# voeding.net
KiCad netlist of a schematic drawn in Altium Designer
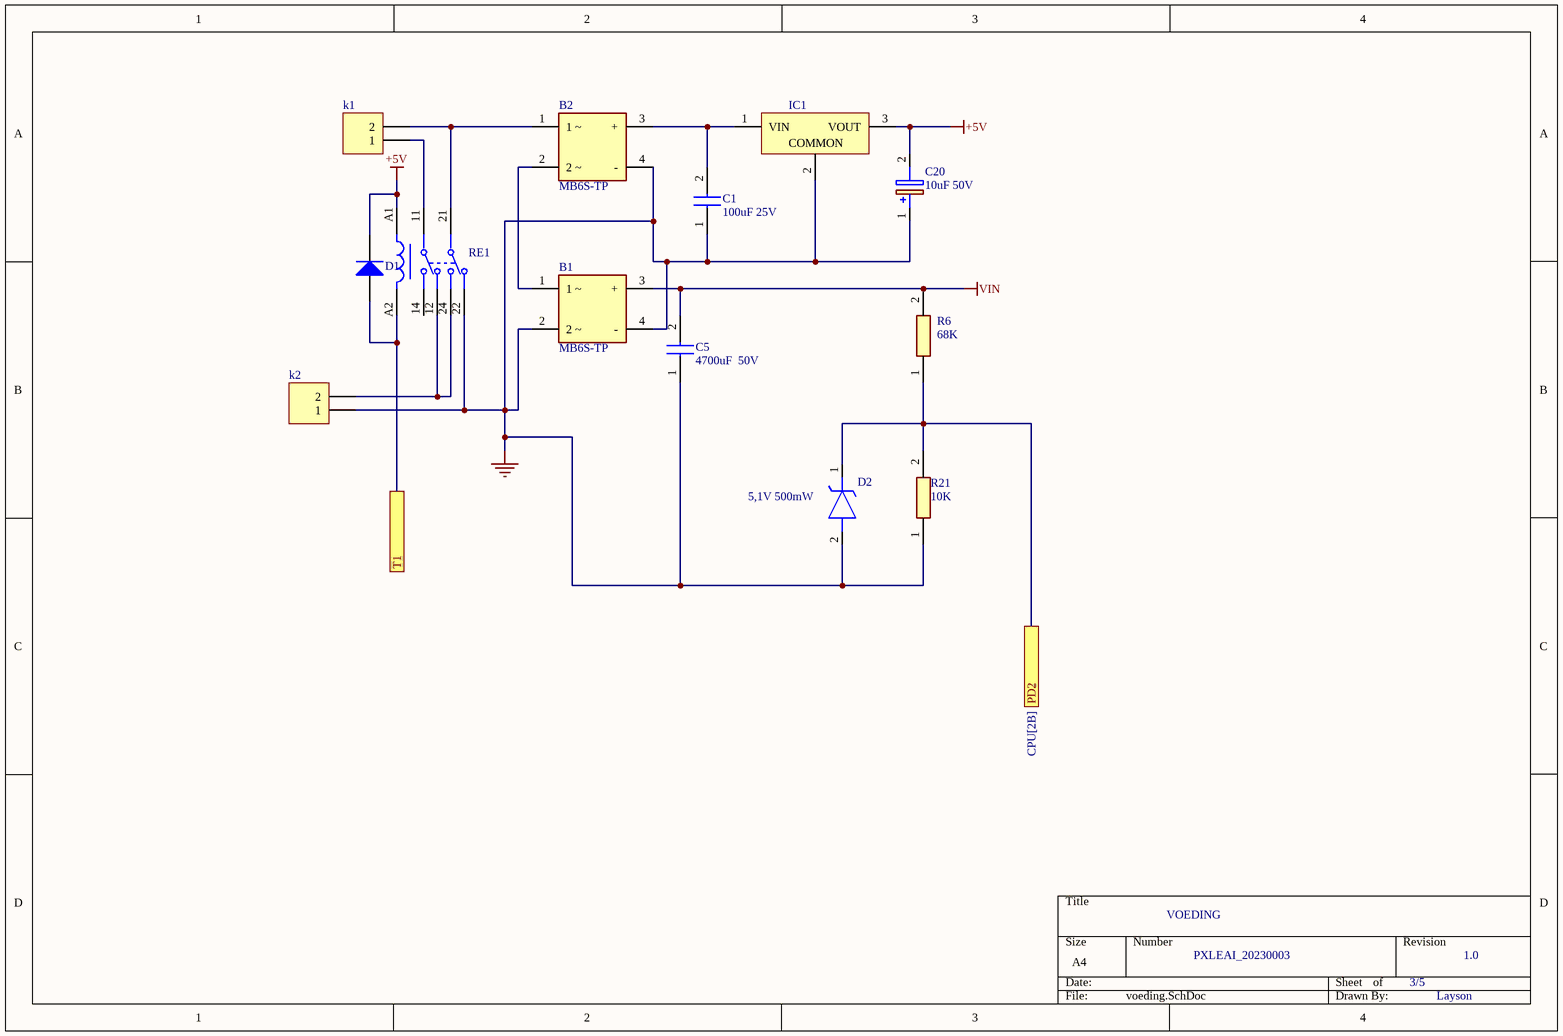
[diagram p0: voeding.SchDoc]

(export (version "E")
  (design (tool "Eeschema 10.0.6"))
  (components
    (comp (ref "B1")
      (value "MB6S-TP")
      (footprint "FP-MBS-1-MFG")
      (description "BRIDGE RECT 1P 600V 500MA MBS-1")
      (fields
        (field (name "OCTOPART") "https://octopart.com/mb6s-tp-mcc-733391")
        (field (name "MANUFACTURER") "MCC")
      )
      (libsource (lib "Altium Content Vault") (part "4d71835a231c4bf99e86ed7a78abdc8"))
    )
    (comp (ref "B2")
      (value "MB6S-TP")
      (footprint "FP-MBS-1-MFG")
      (description "BRIDGE RECT 1P 600V 500MA MBS-1")
      (fields
        (field (name "OCTOPART") "https://octopart.com/mb6s-tp-mcc-733391")
        (field (name "MANUFACTURER") "MCC")
      )
      (libsource (lib "Altium Content Vault") (part "4d71835a231c4bf99e86ed7a78abdc8"))
    )
    (comp (ref "C1")
      (value "100uF 25V")
      (footprint "SamacSys:MCGPR25V107M6.3X11")
      (description "Capacitor\r\nMCGPR25V107M6.3X11")
      (fields (field (name "MANUFACTURER_PART_NUMBER") "MCGPR25V107M6.3X11"))
      (libsource (lib "*") (part "MCGPR25V107M6.3X11"))
    )
    (comp (ref "C5")
      (value "4700uF  50V")
      (footprint "SamacSys:CAPPRD1000W82D2250H4300")
      (description "Capacitor \r\nMCGPR50V478M22X41")
      (fields (field (name "MANUFACTURER_PART_NUMBER") "MCGPR50V478M22X41"))
      (libsource (lib "*") (part "MCGPR50V478M22X41"))
    )
    (comp (ref "C20")
      (value "10uF 50V")
      (footprint "SamacSys:CAPPRD200W52D525H1200")
      (description "Capacitor Polarised\r\nMCGPR50V106M5X11")
      (fields (field (name "MANUFACTURER_PART_NUMBER") "MCGPR50V106M5X11"))
      (libsource (lib "*") (part "MCGPR50V106M5X11"))
    )
    (comp (ref "D1")
      (value "Diode 1N4007")
      (footprint "DO-41")
      (description "1 Amp General Purpose Rectifier")
      (fields (field (name "PUBLISHER") "Altium Limited"))
      (libsource (lib "Miscellaneous Devices") (part "Diode 1N4007"))
    )
    (comp (ref "D2")
      (value "5,1V 500mW")
      (footprint "SamacSys:DIOM5226X240N")
      (description "Zener Diode\r\nSMAZ5V1-13-F")
      (fields
        (field (name "MANUFACTURER_PART_NUMBER") "SMAZ5V1-13-F")
        (field (name "MOUSER PART NUMBER") "621-SMAZ5V1-F")
      )
      (libsource (lib "*") (part "SMAZ5V1-13-F"))
    )
    (comp (ref "IC1")
      (value "OKI-78SR-5/1.5-W36-C")
      (footprint "MURA-OKI-78SR-3")
      (description "Non-Isolated DC/DC Converter, 7.5 W, 7 to 36 V, 1.5 A, -40 to 85 degC, 3-Pin THD, RoHS")
      (fields (field (name "MANUFACTURER") "Murata"))
      (libsource (lib "Altium Content Vault") (part "MURA-OKI-78SR-3"))
    )
    (comp (ref "k1")
      (value "Header 2")
      (footprint "HDR1X2")
      (description "Header, 2-Pin")
      (fields (field (name "PUBLISHER") "Altium Limited"))
      (libsource (lib "Miscellaneous Connectors") (part "Header 2"))
    )
    (comp (ref "k2")
      (value "Header 2")
      (footprint "HDR1X2")
      (description "Header, 2-Pin")
      (fields (field (name "PUBLISHER") "Altium Limited"))
      (libsource (lib "Miscellaneous Connectors") (part "Header 2"))
    )
    (comp (ref "R6")
      (value "68K")
      (footprint "SamacSys:RESC2012X60N")
      (description "Resistor\r\nCR0805-FX-6802GLF")
      (fields
        (field (name "MANUFACTURER_PART_NUMBER") "CR0805-FX-6802GLF")
        (field (name "MOUSER PART NUMBER") "652-CR0805-FX6802GLF")
      )
      (libsource (lib "*") (part "CR0805-FX-6802GLF"))
    )
    (comp (ref "R21")
      (value "10K")
      (footprint "SamacSys:RESC2012X65N")
      (description "Resistor\r\nCPF0805B10KE")
      (fields
        (field (name "MANUFACTURER_PART_NUMBER") "CPF0805B10KE")
        (field (name "MOUSER PART NUMBER") "279-CPF0805B10KE")
      )
      (libsource (lib "*") (part "CPF0805B10KE"))
    )
    (comp (ref "RE1")
      (value "RT424005F")
      (footprint "FP-RT424005F-MFG")
      (description "RELAY GENERAL PURPOSE DPDT 8A 5V")
      (libsource (lib "Altium Content Vault") (part "41b11f646d56a8146f21bf1e8c88c79"))
    )
  )
  (nets
    (net (code "1") (name "+5V") (class "Default")
      (node (ref "C20") (pin "2") (pinfunction "-_2") (pintype "passive"))
      (node (ref "D1") (pin "2") (pinfunction "K_2") (pintype "passive"))
      (node (ref "IC1") (pin "3") (pinfunction "VOUT_3") (pintype "power_in"))
      (node (ref "RE1") (pin "A1") (pinfunction "A1_A1") (pintype "passive"))
    )
    (net (code "2") (name "/PD2") (class "Default")
      (node (ref "D2") (pin "1") (pinfunction "K_1") (pintype "passive"))
      (node (ref "R21") (pin "2") (pinfunction "2_2") (pintype "passive"))
      (node (ref "R6") (pin "1") (pinfunction "1_1") (pintype "passive"))
    )
    (net (code "3") (name "/T1") (class "Default")
      (node (ref "D1") (pin "1") (pinfunction "A_1") (pintype "passive"))
      (node (ref "RE1") (pin "A2") (pinfunction "A2_A2") (pintype "passive"))
    )
    (net (code "4") (name "GND") (class "Default")
      (node (ref "B1") (pin "2") (pinfunction "2_~_2") (pintype "passive"))
      (node (ref "B1") (pin "4") (pinfunction "-_4") (pintype "passive"))
      (node (ref "B2") (pin "4") (pinfunction "-_4") (pintype "passive"))
      (node (ref "C1") (pin "1") (pinfunction "+_1") (pintype "passive"))
      (node (ref "C20") (pin "1") (pinfunction "+_1") (pintype "passive"))
      (node (ref "C5") (pin "1") (pinfunction "+_1") (pintype "passive"))
      (node (ref "D2") (pin "2") (pinfunction "A_2") (pintype "passive"))
      (node (ref "IC1") (pin "2") (pinfunction "COMMON_2") (pintype "power_in"))
      (node (ref "R21") (pin "1") (pinfunction "1_1") (pintype "passive"))
      (node (ref "RE1") (pin "22") (pinfunction "22_22") (pintype "passive"))
      (node (ref "k2") (pin "1") (pinfunction "1_1") (pintype "passive"))
    )
    (net (code "5") (name "Net-(B1-1_~)") (class "Default")
      (node (ref "B1") (pin "1") (pinfunction "1_~_1") (pintype "passive"))
      (node (ref "B2") (pin "2") (pinfunction "2_~_2") (pintype "passive"))
    )
    (net (code "6") (name "Net-(B2-+)") (class "Default")
      (node (ref "B2") (pin "3") (pinfunction "+_3") (pintype "passive"))
      (node (ref "C1") (pin "2") (pinfunction "-_2") (pintype "passive"))
      (node (ref "IC1") (pin "1") (pinfunction "VIN_1") (pintype "power_in"))
    )
    (net (code "7") (name "Net-(B2-1_~)") (class "Default")
      (node (ref "B2") (pin "1") (pinfunction "1_~_1") (pintype "passive"))
      (node (ref "RE1") (pin "21") (pinfunction "21_21") (pintype "passive"))
      (node (ref "k1") (pin "2") (pinfunction "2_2") (pintype "passive"))
    )
    (net (code "8") (name "Net-(RE1-Pad11)") (class "Default")
      (node (ref "RE1") (pin "11") (pinfunction "11_11") (pintype "passive"))
      (node (ref "k1") (pin "1") (pinfunction "1_1") (pintype "passive"))
    )
    (net (code "9") (name "Net-(RE1-Pad12)") (class "Default")
      (node (ref "RE1") (pin "12") (pinfunction "12_12") (pintype "passive"))
      (node (ref "RE1") (pin "24") (pinfunction "24_24") (pintype "passive"))
      (node (ref "k2") (pin "2") (pinfunction "2_2") (pintype "passive"))
    )
    (net (code "10") (name "VIN") (class "Default")
      (node (ref "B1") (pin "3") (pinfunction "+_3") (pintype "passive"))
      (node (ref "C5") (pin "2") (pinfunction "-_2") (pintype "passive"))
      (node (ref "R6") (pin "2") (pinfunction "2_2") (pintype "passive"))
    )
    (net (code "11") (name "unconnected-(RE1-Pad14)") (class "Default")
      (node (ref "RE1") (pin "14") (pinfunction "14_14") (pintype "passive"))
    )
  )
)
